# BLINKING.net
KiCad netlist of a schematic drawn in Altium Designer
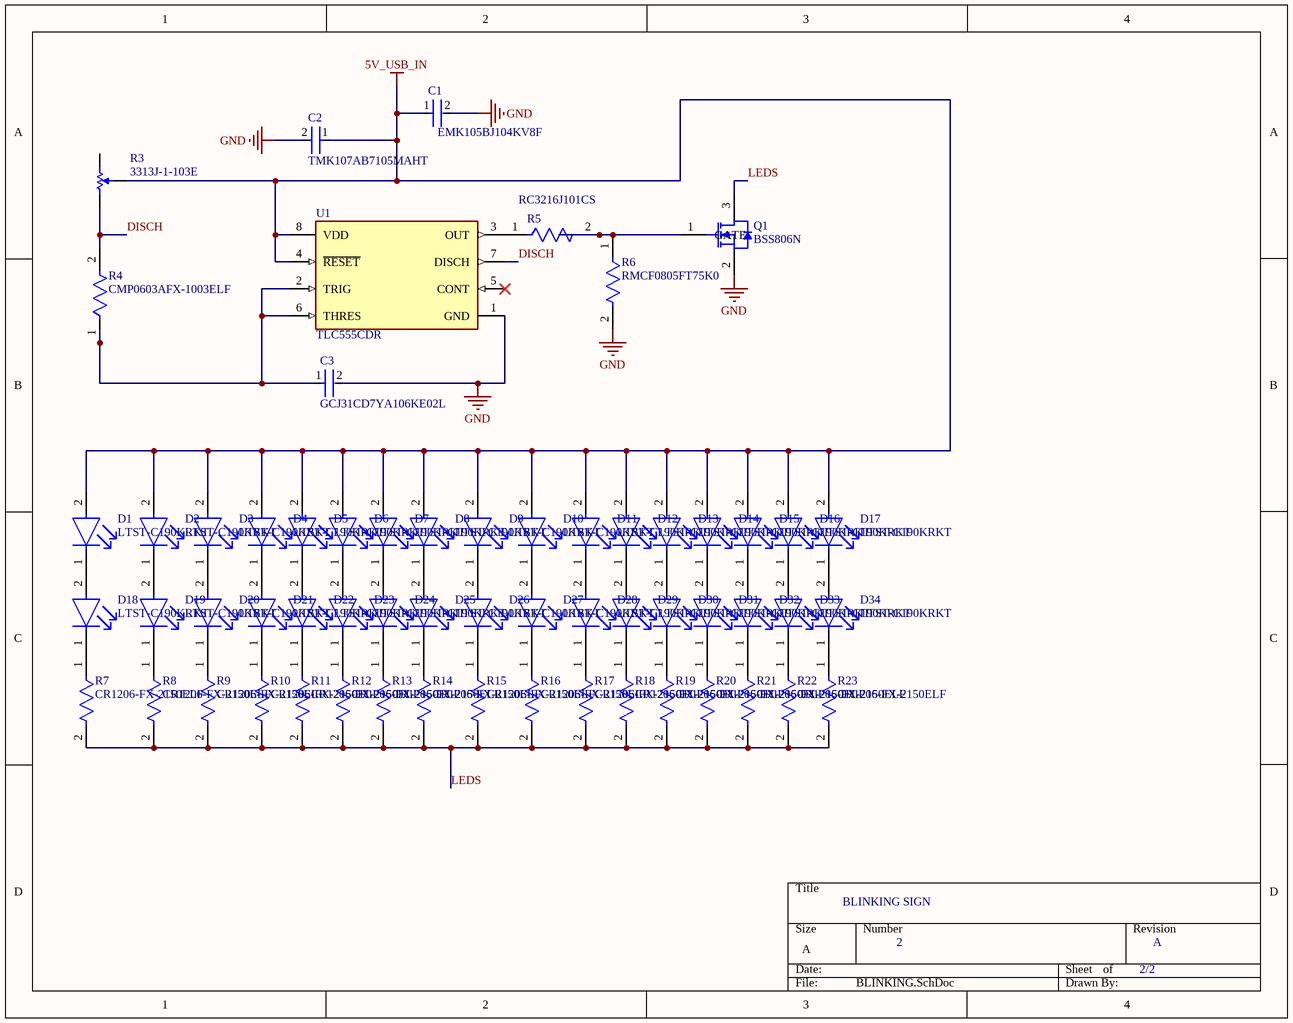
[diagram p0: BLINKING.SchDoc]

(export (version "E")
  (design (tool "Eeschema 10.0.6"))
  (components
    (comp (ref "C1")
      (value "EMK105BJ104KV8F")
      (footprint "FP-0402-L_1_0_0_05-W_0_5-MFG")
      (description "None")
      (libsource (lib "Altium Content Vault") (part "b4654b650e69147ec39a6b967a45e02"))
    )
    (comp (ref "C2")
      (value "TMK107AB7105MAHT")
      (footprint "FP-0603-L_1_6_0_15-W_0_8-IPC_B")
      (description "None")
      (fields (field (name "TOLERANCE") "20%"))
      (libsource (lib "Altium Content Vault") (part "b4654b650e69147ec39a6b967a45e02"))
    )
    (comp (ref "C3")
      (value "GCJ31CD7YA106KE02L")
      (footprint "FP-GCJ31C-0_4-IPC_C")
      (description "Cap Ceramic 10uF 35V X7T 10% SMD 1206 +125°C Embossed Plastic T/R")
      (libsource (lib "Altium Content Vault") (part "02cd4be3c70576c341d710602a673aa"))
    )
    (comp (ref "D1")
      (value "LTST-C190KRKT")
      (footprint "FP-LTST-C190KRKT-MFG")
      (description "LED RED CLEAR CHIP SMD")
      (libsource (lib "Altium Content Vault") (part "8706943c75ba83719d021d2fdc84c58"))
    )
    (comp (ref "D2")
      (value "LTST-C190KRKT")
      (footprint "FP-LTST-C190KRKT-MFG")
      (description "LED RED CLEAR CHIP SMD")
      (libsource (lib "Altium Content Vault") (part "8706943c75ba83719d021d2fdc84c58"))
    )
    (comp (ref "D3")
      (value "LTST-C190KRKT")
      (footprint "FP-LTST-C190KRKT-MFG")
      (description "LED RED CLEAR CHIP SMD")
      (libsource (lib "Altium Content Vault") (part "8706943c75ba83719d021d2fdc84c58"))
    )
    (comp (ref "D4")
      (value "LTST-C190KRKT")
      (footprint "FP-LTST-C190KRKT-MFG")
      (description "LED RED CLEAR CHIP SMD")
      (libsource (lib "Altium Content Vault") (part "8706943c75ba83719d021d2fdc84c58"))
    )
    (comp (ref "D5")
      (value "LTST-C190KRKT")
      (footprint "FP-LTST-C190KRKT-MFG")
      (description "LED RED CLEAR CHIP SMD")
      (libsource (lib "Altium Content Vault") (part "8706943c75ba83719d021d2fdc84c58"))
    )
    (comp (ref "D6")
      (value "LTST-C190KRKT")
      (footprint "FP-LTST-C190KRKT-MFG")
      (description "LED RED CLEAR CHIP SMD")
      (libsource (lib "Altium Content Vault") (part "8706943c75ba83719d021d2fdc84c58"))
    )
    (comp (ref "D7")
      (value "LTST-C190KRKT")
      (footprint "FP-LTST-C190KRKT-MFG")
      (description "LED RED CLEAR CHIP SMD")
      (libsource (lib "Altium Content Vault") (part "8706943c75ba83719d021d2fdc84c58"))
    )
    (comp (ref "D8")
      (value "LTST-C190KRKT")
      (footprint "FP-LTST-C190KRKT-MFG")
      (description "LED RED CLEAR CHIP SMD")
      (libsource (lib "Altium Content Vault") (part "8706943c75ba83719d021d2fdc84c58"))
    )
    (comp (ref "D9")
      (value "LTST-C190KRKT")
      (footprint "FP-LTST-C190KRKT-MFG")
      (description "LED RED CLEAR CHIP SMD")
      (libsource (lib "Altium Content Vault") (part "8706943c75ba83719d021d2fdc84c58"))
    )
    (comp (ref "D10")
      (value "LTST-C190KRKT")
      (footprint "FP-LTST-C190KRKT-MFG")
      (description "LED RED CLEAR CHIP SMD")
      (libsource (lib "Altium Content Vault") (part "8706943c75ba83719d021d2fdc84c58"))
    )
    (comp (ref "D11")
      (value "LTST-C190KRKT")
      (footprint "FP-LTST-C190KRKT-MFG")
      (description "LED RED CLEAR CHIP SMD")
      (libsource (lib "Altium Content Vault") (part "8706943c75ba83719d021d2fdc84c58"))
    )
    (comp (ref "D12")
      (value "LTST-C190KRKT")
      (footprint "FP-LTST-C190KRKT-MFG")
      (description "LED RED CLEAR CHIP SMD")
      (libsource (lib "Altium Content Vault") (part "8706943c75ba83719d021d2fdc84c58"))
    )
    (comp (ref "D13")
      (value "LTST-C190KRKT")
      (footprint "FP-LTST-C190KRKT-MFG")
      (description "LED RED CLEAR CHIP SMD")
      (libsource (lib "Altium Content Vault") (part "8706943c75ba83719d021d2fdc84c58"))
    )
    (comp (ref "D14")
      (value "LTST-C190KRKT")
      (footprint "FP-LTST-C190KRKT-MFG")
      (description "LED RED CLEAR CHIP SMD")
      (libsource (lib "Altium Content Vault") (part "8706943c75ba83719d021d2fdc84c58"))
    )
    (comp (ref "D15")
      (value "LTST-C190KRKT")
      (footprint "FP-LTST-C190KRKT-MFG")
      (description "LED RED CLEAR CHIP SMD")
      (libsource (lib "Altium Content Vault") (part "8706943c75ba83719d021d2fdc84c58"))
    )
    (comp (ref "D16")
      (value "LTST-C190KRKT")
      (footprint "FP-LTST-C190KRKT-MFG")
      (description "LED RED CLEAR CHIP SMD")
      (libsource (lib "Altium Content Vault") (part "8706943c75ba83719d021d2fdc84c58"))
    )
    (comp (ref "D17")
      (value "LTST-C190KRKT")
      (footprint "FP-LTST-C190KRKT-MFG")
      (description "LED RED CLEAR CHIP SMD")
      (libsource (lib "Altium Content Vault") (part "8706943c75ba83719d021d2fdc84c58"))
    )
    (comp (ref "D18")
      (value "LTST-C190KRKT")
      (footprint "FP-LTST-C190KRKT-MFG")
      (description "LED RED CLEAR CHIP SMD")
      (libsource (lib "Altium Content Vault") (part "8706943c75ba83719d021d2fdc84c58"))
    )
    (comp (ref "D19")
      (value "LTST-C190KRKT")
      (footprint "FP-LTST-C190KRKT-MFG")
      (description "LED RED CLEAR CHIP SMD")
      (libsource (lib "Altium Content Vault") (part "8706943c75ba83719d021d2fdc84c58"))
    )
    (comp (ref "D20")
      (value "LTST-C190KRKT")
      (footprint "FP-LTST-C190KRKT-MFG")
      (description "LED RED CLEAR CHIP SMD")
      (libsource (lib "Altium Content Vault") (part "8706943c75ba83719d021d2fdc84c58"))
    )
    (comp (ref "D21")
      (value "LTST-C190KRKT")
      (footprint "FP-LTST-C190KRKT-MFG")
      (description "LED RED CLEAR CHIP SMD")
      (libsource (lib "Altium Content Vault") (part "8706943c75ba83719d021d2fdc84c58"))
    )
    (comp (ref "D22")
      (value "LTST-C190KRKT")
      (footprint "FP-LTST-C190KRKT-MFG")
      (description "LED RED CLEAR CHIP SMD")
      (libsource (lib "Altium Content Vault") (part "8706943c75ba83719d021d2fdc84c58"))
    )
    (comp (ref "D23")
      (value "LTST-C190KRKT")
      (footprint "FP-LTST-C190KRKT-MFG")
      (description "LED RED CLEAR CHIP SMD")
      (libsource (lib "Altium Content Vault") (part "8706943c75ba83719d021d2fdc84c58"))
    )
    (comp (ref "D24")
      (value "LTST-C190KRKT")
      (footprint "FP-LTST-C190KRKT-MFG")
      (description "LED RED CLEAR CHIP SMD")
      (libsource (lib "Altium Content Vault") (part "8706943c75ba83719d021d2fdc84c58"))
    )
    (comp (ref "D25")
      (value "LTST-C190KRKT")
      (footprint "FP-LTST-C190KRKT-MFG")
      (description "LED RED CLEAR CHIP SMD")
      (libsource (lib "Altium Content Vault") (part "8706943c75ba83719d021d2fdc84c58"))
    )
    (comp (ref "D26")
      (value "LTST-C190KRKT")
      (footprint "FP-LTST-C190KRKT-MFG")
      (description "LED RED CLEAR CHIP SMD")
      (libsource (lib "Altium Content Vault") (part "8706943c75ba83719d021d2fdc84c58"))
    )
    (comp (ref "D27")
      (value "LTST-C190KRKT")
      (footprint "FP-LTST-C190KRKT-MFG")
      (description "LED RED CLEAR CHIP SMD")
      (libsource (lib "Altium Content Vault") (part "8706943c75ba83719d021d2fdc84c58"))
    )
    (comp (ref "D28")
      (value "LTST-C190KRKT")
      (footprint "FP-LTST-C190KRKT-MFG")
      (description "LED RED CLEAR CHIP SMD")
      (libsource (lib "Altium Content Vault") (part "8706943c75ba83719d021d2fdc84c58"))
    )
    (comp (ref "D29")
      (value "LTST-C190KRKT")
      (footprint "FP-LTST-C190KRKT-MFG")
      (description "LED RED CLEAR CHIP SMD")
      (libsource (lib "Altium Content Vault") (part "8706943c75ba83719d021d2fdc84c58"))
    )
    (comp (ref "D30")
      (value "LTST-C190KRKT")
      (footprint "FP-LTST-C190KRKT-MFG")
      (description "LED RED CLEAR CHIP SMD")
      (libsource (lib "Altium Content Vault") (part "8706943c75ba83719d021d2fdc84c58"))
    )
    (comp (ref "D31")
      (value "LTST-C190KRKT")
      (footprint "FP-LTST-C190KRKT-MFG")
      (description "LED RED CLEAR CHIP SMD")
      (libsource (lib "Altium Content Vault") (part "8706943c75ba83719d021d2fdc84c58"))
    )
    (comp (ref "D32")
      (value "LTST-C190KRKT")
      (footprint "FP-LTST-C190KRKT-MFG")
      (description "LED RED CLEAR CHIP SMD")
      (libsource (lib "Altium Content Vault") (part "8706943c75ba83719d021d2fdc84c58"))
    )
    (comp (ref "D33")
      (value "LTST-C190KRKT")
      (footprint "FP-LTST-C190KRKT-MFG")
      (description "LED RED CLEAR CHIP SMD")
      (libsource (lib "Altium Content Vault") (part "8706943c75ba83719d021d2fdc84c58"))
    )
    (comp (ref "D34")
      (value "LTST-C190KRKT")
      (footprint "FP-LTST-C190KRKT-MFG")
      (description "LED RED CLEAR CHIP SMD")
      (libsource (lib "Altium Content Vault") (part "8706943c75ba83719d021d2fdc84c58"))
    )
    (comp (ref "Q1")
      (value "BSS806N")
      (footprint "INF-PG-SOT23_M")
      (fields (field (name "MANUFACTURER") "Infineon"))
      (libsource (lib "Altium Content Vault") (part "INF-NEMOS-GSD-3"))
    )
    (comp (ref "R3")
      (value "3313J-1-103E")
      (footprint "BOUR-3313J-1_V")
      (description "Trimming Potentiometer, 10 KOhm, -55 to 125 degC, 3-Pin SMD, RoHS, Tape and Reel")
      (fields (field (name "MANUFACTURER") "Bourns"))
      (libsource (lib "Altium Content Vault") (part "RES-ADJ-3_A"))
    )
    (comp (ref "R4")
      (value "CMP0603AFX-1003ELF")
      (footprint "FP-CMP0603A-MFG")
      (description "RESHIGHPOWERA 0603 100K 1% 1/4W")
      (libsource (lib "Altium Content Vault") (part "1029c3af85768c4190bb7ad29bc67b5"))
    )
    (comp (ref "R5")
      (value "RC3216J101CS")
      (footprint "FP-RC3216-IPC_B")
      (description "Res Thick Film 1206 100Ω 5% 0.25W ±100ppm/°C Molded SMD T/R")
      (fields (field (name "TOLERANCE") "5%"))
      (libsource (lib "Altium Content Vault") (part "1029c3af85768c4190bb7ad29bc67b5"))
    )
    (comp (ref "R6")
      (value "RMCF0805FT75K0")
      (footprint "FP-RMCF0805-IPC_B")
      (description "75kΩ ±1% 0.125W 0805 Thick Film Chip Resistor AEC-Q200 compliant")
      (fields (field (name "TOLERANCE") "1%"))
      (libsource (lib "Altium Content Vault") (part "1029c3af85768c4190bb7ad29bc67b5"))
    )
    (comp (ref "R7")
      (value "CR1206-FX-2150ELF")
      (footprint "FP-CR1206-IPC_B")
      (description "Thick Film Chip Resistors 1206 215Ω 0.25W 1% 100ppm/°C")
      (fields (field (name "TOLERANCE") "1%"))
      (libsource (lib "Altium Content Vault") (part "1029c3af85768c4190bb7ad29bc67b5"))
    )
    (comp (ref "R8")
      (value "CR1206-FX-2150ELF")
      (footprint "FP-CR1206-IPC_B")
      (description "Thick Film Chip Resistors 1206 215Ω 0.25W 1% 100ppm/°C")
      (fields (field (name "TOLERANCE") "1%"))
      (libsource (lib "Altium Content Vault") (part "1029c3af85768c4190bb7ad29bc67b5"))
    )
    (comp (ref "R9")
      (value "CR1206-FX-2150ELF")
      (footprint "FP-CR1206-IPC_B")
      (description "Thick Film Chip Resistors 1206 215Ω 0.25W 1% 100ppm/°C")
      (fields (field (name "TOLERANCE") "1%"))
      (libsource (lib "Altium Content Vault") (part "1029c3af85768c4190bb7ad29bc67b5"))
    )
    (comp (ref "R10")
      (value "CR1206-FX-2150ELF")
      (footprint "FP-CR1206-IPC_B")
      (description "Thick Film Chip Resistors 1206 215Ω 0.25W 1% 100ppm/°C")
      (fields (field (name "TOLERANCE") "1%"))
      (libsource (lib "Altium Content Vault") (part "1029c3af85768c4190bb7ad29bc67b5"))
    )
    (comp (ref "R11")
      (value "CR1206-FX-2150ELF")
      (footprint "FP-CR1206-IPC_B")
      (description "Thick Film Chip Resistors 1206 215Ω 0.25W 1% 100ppm/°C")
      (fields (field (name "TOLERANCE") "1%"))
      (libsource (lib "Altium Content Vault") (part "1029c3af85768c4190bb7ad29bc67b5"))
    )
    (comp (ref "R12")
      (value "CR1206-FX-2150ELF")
      (footprint "FP-CR1206-IPC_B")
      (description "Thick Film Chip Resistors 1206 215Ω 0.25W 1% 100ppm/°C")
      (fields (field (name "TOLERANCE") "1%"))
      (libsource (lib "Altium Content Vault") (part "1029c3af85768c4190bb7ad29bc67b5"))
    )
    (comp (ref "R13")
      (value "CR1206-FX-2150ELF")
      (footprint "FP-CR1206-IPC_B")
      (description "Thick Film Chip Resistors 1206 215Ω 0.25W 1% 100ppm/°C")
      (fields (field (name "TOLERANCE") "1%"))
      (libsource (lib "Altium Content Vault") (part "1029c3af85768c4190bb7ad29bc67b5"))
    )
    (comp (ref "R14")
      (value "CR1206-FX-2150ELF")
      (footprint "FP-CR1206-IPC_B")
      (description "Thick Film Chip Resistors 1206 215Ω 0.25W 1% 100ppm/°C")
      (fields (field (name "TOLERANCE") "1%"))
      (libsource (lib "Altium Content Vault") (part "1029c3af85768c4190bb7ad29bc67b5"))
    )
    (comp (ref "R15")
      (value "CR1206-FX-2150ELF")
      (footprint "FP-CR1206-IPC_B")
      (description "Thick Film Chip Resistors 1206 215Ω 0.25W 1% 100ppm/°C")
      (fields (field (name "TOLERANCE") "1%"))
      (libsource (lib "Altium Content Vault") (part "1029c3af85768c4190bb7ad29bc67b5"))
    )
    (comp (ref "R16")
      (value "CR1206-FX-2150ELF")
      (footprint "FP-CR1206-IPC_B")
      (description "Thick Film Chip Resistors 1206 215Ω 0.25W 1% 100ppm/°C")
      (fields (field (name "TOLERANCE") "1%"))
      (libsource (lib "Altium Content Vault") (part "1029c3af85768c4190bb7ad29bc67b5"))
    )
    (comp (ref "R17")
      (value "CR1206-FX-2150ELF")
      (footprint "FP-CR1206-IPC_B")
      (description "Thick Film Chip Resistors 1206 215Ω 0.25W 1% 100ppm/°C")
      (fields (field (name "TOLERANCE") "1%"))
      (libsource (lib "Altium Content Vault") (part "1029c3af85768c4190bb7ad29bc67b5"))
    )
    (comp (ref "R18")
      (value "CR1206-FX-2150ELF")
      (footprint "FP-CR1206-IPC_B")
      (description "Thick Film Chip Resistors 1206 215Ω 0.25W 1% 100ppm/°C")
      (fields (field (name "TOLERANCE") "1%"))
      (libsource (lib "Altium Content Vault") (part "1029c3af85768c4190bb7ad29bc67b5"))
    )
    (comp (ref "R19")
      (value "CR1206-FX-2150ELF")
      (footprint "FP-CR1206-IPC_B")
      (description "Thick Film Chip Resistors 1206 215Ω 0.25W 1% 100ppm/°C")
      (fields (field (name "TOLERANCE") "1%"))
      (libsource (lib "Altium Content Vault") (part "1029c3af85768c4190bb7ad29bc67b5"))
    )
    (comp (ref "R20")
      (value "CR1206-FX-2150ELF")
      (footprint "FP-CR1206-IPC_B")
      (description "Thick Film Chip Resistors 1206 215Ω 0.25W 1% 100ppm/°C")
      (fields (field (name "TOLERANCE") "1%"))
      (libsource (lib "Altium Content Vault") (part "1029c3af85768c4190bb7ad29bc67b5"))
    )
    (comp (ref "R21")
      (value "CR1206-FX-2150ELF")
      (footprint "FP-CR1206-IPC_B")
      (description "Thick Film Chip Resistors 1206 215Ω 0.25W 1% 100ppm/°C")
      (fields (field (name "TOLERANCE") "1%"))
      (libsource (lib "Altium Content Vault") (part "1029c3af85768c4190bb7ad29bc67b5"))
    )
    (comp (ref "R22")
      (value "CR1206-FX-2150ELF")
      (footprint "FP-CR1206-IPC_B")
      (description "Thick Film Chip Resistors 1206 215Ω 0.25W 1% 100ppm/°C")
      (fields (field (name "TOLERANCE") "1%"))
      (libsource (lib "Altium Content Vault") (part "1029c3af85768c4190bb7ad29bc67b5"))
    )
    (comp (ref "R23")
      (value "CR1206-FX-2150ELF")
      (footprint "FP-CR1206-IPC_B")
      (description "Thick Film Chip Resistors 1206 215Ω 0.25W 1% 100ppm/°C")
      (fields (field (name "TOLERANCE") "1%"))
      (libsource (lib "Altium Content Vault") (part "1029c3af85768c4190bb7ad29bc67b5"))
    )
    (comp (ref "U1")
      (value "TLC555CDR")
      (footprint "FP-D0008A-IPC_B")
      (description "IC OSC SGL TIMER 2.1MHZ 8-SOIC")
      (libsource (lib "Altium Content Vault") (part "fd1638d23bf5e420a54176ee4f8e783"))
    )
  )
  (nets
    (net (code "1") (name "/DISCH") (class "Default")
      (node (ref "R3") (pin "1") (pinfunction "1_1") (pintype "passive"))
      (node (ref "R4") (pin "2") (pinfunction "2_2") (pintype "passive"))
      (node (ref "U1") (pin "7") (pinfunction "DISCH_7") (pintype "output"))
    )
    (net (code "2") (name "/LEDS") (class "Default")
      (node (ref "Q1") (pin "3") (pinfunction "DRAIN_3") (pintype "passive"))
      (node (ref "R10") (pin "2") (pinfunction "2_2") (pintype "passive"))
      (node (ref "R11") (pin "2") (pinfunction "2_2") (pintype "passive"))
      (node (ref "R12") (pin "2") (pinfunction "2_2") (pintype "passive"))
      (node (ref "R13") (pin "2") (pinfunction "2_2") (pintype "passive"))
      (node (ref "R14") (pin "2") (pinfunction "2_2") (pintype "passive"))
      (node (ref "R15") (pin "2") (pinfunction "2_2") (pintype "passive"))
      (node (ref "R16") (pin "2") (pinfunction "2_2") (pintype "passive"))
      (node (ref "R17") (pin "2") (pinfunction "2_2") (pintype "passive"))
      (node (ref "R18") (pin "2") (pinfunction "2_2") (pintype "passive"))
      (node (ref "R19") (pin "2") (pinfunction "2_2") (pintype "passive"))
      (node (ref "R20") (pin "2") (pinfunction "2_2") (pintype "passive"))
      (node (ref "R21") (pin "2") (pinfunction "2_2") (pintype "passive"))
      (node (ref "R22") (pin "2") (pinfunction "2_2") (pintype "passive"))
      (node (ref "R23") (pin "2") (pinfunction "2_2") (pintype "passive"))
      (node (ref "R7") (pin "2") (pinfunction "2_2") (pintype "passive"))
      (node (ref "R8") (pin "2") (pinfunction "2_2") (pintype "passive"))
      (node (ref "R9") (pin "2") (pinfunction "2_2") (pintype "passive"))
    )
    (net (code "3") (name "5V_USB_IN") (class "Default")
      (node (ref "C1") (pin "1") (pinfunction "1_1") (pintype "passive"))
      (node (ref "C2") (pin "1") (pinfunction "1_1") (pintype "passive"))
      (node (ref "D1") (pin "2") (pinfunction "A_2") (pintype "passive"))
      (node (ref "D10") (pin "2") (pinfunction "A_2") (pintype "passive"))
      (node (ref "D11") (pin "2") (pinfunction "A_2") (pintype "passive"))
      (node (ref "D12") (pin "2") (pinfunction "A_2") (pintype "passive"))
      (node (ref "D13") (pin "2") (pinfunction "A_2") (pintype "passive"))
      (node (ref "D14") (pin "2") (pinfunction "A_2") (pintype "passive"))
      (node (ref "D15") (pin "2") (pinfunction "A_2") (pintype "passive"))
      (node (ref "D16") (pin "2") (pinfunction "A_2") (pintype "passive"))
      (node (ref "D17") (pin "2") (pinfunction "A_2") (pintype "passive"))
      (node (ref "D2") (pin "2") (pinfunction "A_2") (pintype "passive"))
      (node (ref "D3") (pin "2") (pinfunction "A_2") (pintype "passive"))
      (node (ref "D4") (pin "2") (pinfunction "A_2") (pintype "passive"))
      (node (ref "D5") (pin "2") (pinfunction "A_2") (pintype "passive"))
      (node (ref "D6") (pin "2") (pinfunction "A_2") (pintype "passive"))
      (node (ref "D7") (pin "2") (pinfunction "A_2") (pintype "passive"))
      (node (ref "D8") (pin "2") (pinfunction "A_2") (pintype "passive"))
      (node (ref "D9") (pin "2") (pinfunction "A_2") (pintype "passive"))
      (node (ref "R3") (pin "2") (pinfunction "2_2") (pintype "passive"))
      (node (ref "U1") (pin "4") (pinfunction "~{RESET}_4") (pintype "input"))
      (node (ref "U1") (pin "8") (pinfunction "VDD_8") (pintype "power_in"))
    )
    (net (code "4") (name "GND") (class "Default")
      (node (ref "C1") (pin "2") (pinfunction "2_2") (pintype "passive"))
      (node (ref "C2") (pin "2") (pinfunction "2_2") (pintype "passive"))
      (node (ref "C3") (pin "2") (pinfunction "2_2") (pintype "passive"))
      (node (ref "Q1") (pin "2") (pinfunction "SOURCE_2") (pintype "passive"))
      (node (ref "R6") (pin "2") (pinfunction "2_2") (pintype "passive"))
      (node (ref "U1") (pin "1") (pinfunction "GND_1") (pintype "power_in"))
    )
    (net (code "5") (name "Net-(D1-C)") (class "Default")
      (node (ref "D1") (pin "1") (pinfunction "C_1") (pintype "passive"))
      (node (ref "D18") (pin "2") (pinfunction "A_2") (pintype "passive"))
    )
    (net (code "6") (name "Net-(D10-C)") (class "Default")
      (node (ref "D10") (pin "1") (pinfunction "C_1") (pintype "passive"))
      (node (ref "D27") (pin "2") (pinfunction "A_2") (pintype "passive"))
    )
    (net (code "7") (name "Net-(D11-C)") (class "Default")
      (node (ref "D11") (pin "1") (pinfunction "C_1") (pintype "passive"))
      (node (ref "D28") (pin "2") (pinfunction "A_2") (pintype "passive"))
    )
    (net (code "8") (name "Net-(D12-C)") (class "Default")
      (node (ref "D12") (pin "1") (pinfunction "C_1") (pintype "passive"))
      (node (ref "D29") (pin "2") (pinfunction "A_2") (pintype "passive"))
    )
    (net (code "9") (name "Net-(D13-C)") (class "Default")
      (node (ref "D13") (pin "1") (pinfunction "C_1") (pintype "passive"))
      (node (ref "D30") (pin "2") (pinfunction "A_2") (pintype "passive"))
    )
    (net (code "10") (name "Net-(D14-C)") (class "Default")
      (node (ref "D14") (pin "1") (pinfunction "C_1") (pintype "passive"))
      (node (ref "D31") (pin "2") (pinfunction "A_2") (pintype "passive"))
    )
    (net (code "11") (name "Net-(D15-C)") (class "Default")
      (node (ref "D15") (pin "1") (pinfunction "C_1") (pintype "passive"))
      (node (ref "D32") (pin "2") (pinfunction "A_2") (pintype "passive"))
    )
    (net (code "12") (name "Net-(D16-C)") (class "Default")
      (node (ref "D16") (pin "1") (pinfunction "C_1") (pintype "passive"))
      (node (ref "D33") (pin "2") (pinfunction "A_2") (pintype "passive"))
    )
    (net (code "13") (name "Net-(D17-C)") (class "Default")
      (node (ref "D17") (pin "1") (pinfunction "C_1") (pintype "passive"))
      (node (ref "D34") (pin "2") (pinfunction "A_2") (pintype "passive"))
    )
    (net (code "14") (name "Net-(D18-C)") (class "Default")
      (node (ref "D18") (pin "1") (pinfunction "C_1") (pintype "passive"))
      (node (ref "R7") (pin "1") (pinfunction "1_1") (pintype "passive"))
    )
    (net (code "15") (name "Net-(D19-A)") (class "Default")
      (node (ref "D19") (pin "2") (pinfunction "A_2") (pintype "passive"))
      (node (ref "D2") (pin "1") (pinfunction "C_1") (pintype "passive"))
    )
    (net (code "16") (name "Net-(D19-C)") (class "Default")
      (node (ref "D19") (pin "1") (pinfunction "C_1") (pintype "passive"))
      (node (ref "R8") (pin "1") (pinfunction "1_1") (pintype "passive"))
    )
    (net (code "17") (name "Net-(D20-A)") (class "Default")
      (node (ref "D20") (pin "2") (pinfunction "A_2") (pintype "passive"))
      (node (ref "D3") (pin "1") (pinfunction "C_1") (pintype "passive"))
    )
    (net (code "18") (name "Net-(D20-C)") (class "Default")
      (node (ref "D20") (pin "1") (pinfunction "C_1") (pintype "passive"))
      (node (ref "R9") (pin "1") (pinfunction "1_1") (pintype "passive"))
    )
    (net (code "19") (name "Net-(D21-A)") (class "Default")
      (node (ref "D21") (pin "2") (pinfunction "A_2") (pintype "passive"))
      (node (ref "D4") (pin "1") (pinfunction "C_1") (pintype "passive"))
    )
    (net (code "20") (name "Net-(D21-C)") (class "Default")
      (node (ref "D21") (pin "1") (pinfunction "C_1") (pintype "passive"))
      (node (ref "R10") (pin "1") (pinfunction "1_1") (pintype "passive"))
    )
    (net (code "21") (name "Net-(D22-A)") (class "Default")
      (node (ref "D22") (pin "2") (pinfunction "A_2") (pintype "passive"))
      (node (ref "D5") (pin "1") (pinfunction "C_1") (pintype "passive"))
    )
    (net (code "22") (name "Net-(D22-C)") (class "Default")
      (node (ref "D22") (pin "1") (pinfunction "C_1") (pintype "passive"))
      (node (ref "R11") (pin "1") (pinfunction "1_1") (pintype "passive"))
    )
    (net (code "23") (name "Net-(D23-A)") (class "Default")
      (node (ref "D23") (pin "2") (pinfunction "A_2") (pintype "passive"))
      (node (ref "D6") (pin "1") (pinfunction "C_1") (pintype "passive"))
    )
    (net (code "24") (name "Net-(D23-C)") (class "Default")
      (node (ref "D23") (pin "1") (pinfunction "C_1") (pintype "passive"))
      (node (ref "R12") (pin "1") (pinfunction "1_1") (pintype "passive"))
    )
    (net (code "25") (name "Net-(D24-A)") (class "Default")
      (node (ref "D24") (pin "2") (pinfunction "A_2") (pintype "passive"))
      (node (ref "D7") (pin "1") (pinfunction "C_1") (pintype "passive"))
    )
    (net (code "26") (name "Net-(D24-C)") (class "Default")
      (node (ref "D24") (pin "1") (pinfunction "C_1") (pintype "passive"))
      (node (ref "R13") (pin "1") (pinfunction "1_1") (pintype "passive"))
    )
    (net (code "27") (name "Net-(D25-A)") (class "Default")
      (node (ref "D25") (pin "2") (pinfunction "A_2") (pintype "passive"))
      (node (ref "D8") (pin "1") (pinfunction "C_1") (pintype "passive"))
    )
    (net (code "28") (name "Net-(D25-C)") (class "Default")
      (node (ref "D25") (pin "1") (pinfunction "C_1") (pintype "passive"))
      (node (ref "R14") (pin "1") (pinfunction "1_1") (pintype "passive"))
    )
    (net (code "29") (name "Net-(D26-A)") (class "Default")
      (node (ref "D26") (pin "2") (pinfunction "A_2") (pintype "passive"))
      (node (ref "D9") (pin "1") (pinfunction "C_1") (pintype "passive"))
    )
    (net (code "30") (name "Net-(D26-C)") (class "Default")
      (node (ref "D26") (pin "1") (pinfunction "C_1") (pintype "passive"))
      (node (ref "R15") (pin "1") (pinfunction "1_1") (pintype "passive"))
    )
    (net (code "31") (name "Net-(D27-C)") (class "Default")
      (node (ref "D27") (pin "1") (pinfunction "C_1") (pintype "passive"))
      (node (ref "R16") (pin "1") (pinfunction "1_1") (pintype "passive"))
    )
    (net (code "32") (name "Net-(D28-C)") (class "Default")
      (node (ref "D28") (pin "1") (pinfunction "C_1") (pintype "passive"))
      (node (ref "R17") (pin "1") (pinfunction "1_1") (pintype "passive"))
    )
    (net (code "33") (name "Net-(D29-C)") (class "Default")
      (node (ref "D29") (pin "1") (pinfunction "C_1") (pintype "passive"))
      (node (ref "R18") (pin "1") (pinfunction "1_1") (pintype "passive"))
    )
    (net (code "34") (name "Net-(D30-C)") (class "Default")
      (node (ref "D30") (pin "1") (pinfunction "C_1") (pintype "passive"))
      (node (ref "R19") (pin "1") (pinfunction "1_1") (pintype "passive"))
    )
    (net (code "35") (name "Net-(D31-C)") (class "Default")
      (node (ref "D31") (pin "1") (pinfunction "C_1") (pintype "passive"))
      (node (ref "R20") (pin "1") (pinfunction "1_1") (pintype "passive"))
    )
    (net (code "36") (name "Net-(D32-C)") (class "Default")
      (node (ref "D32") (pin "1") (pinfunction "C_1") (pintype "passive"))
      (node (ref "R21") (pin "1") (pinfunction "1_1") (pintype "passive"))
    )
    (net (code "37") (name "Net-(D33-C)") (class "Default")
      (node (ref "D33") (pin "1") (pinfunction "C_1") (pintype "passive"))
      (node (ref "R22") (pin "1") (pinfunction "1_1") (pintype "passive"))
    )
    (net (code "38") (name "Net-(D34-C)") (class "Default")
      (node (ref "D34") (pin "1") (pinfunction "C_1") (pintype "passive"))
      (node (ref "R23") (pin "1") (pinfunction "1_1") (pintype "passive"))
    )
    (net (code "39") (name "Net-(Q1-GATE)") (class "Default")
      (node (ref "Q1") (pin "1") (pinfunction "GATE_1") (pintype "passive"))
      (node (ref "R5") (pin "2") (pinfunction "2_2") (pintype "passive"))
      (node (ref "R6") (pin "1") (pinfunction "1_1") (pintype "passive"))
    )
    (net (code "40") (name "Net-(U1-OUT)") (class "Default")
      (node (ref "R5") (pin "1") (pinfunction "1_1") (pintype "passive"))
      (node (ref "U1") (pin "3") (pinfunction "OUT_3") (pintype "output"))
    )
    (net (code "41") (name "Net-(U1-THRES)") (class "Default")
      (node (ref "C3") (pin "1") (pinfunction "1_1") (pintype "passive"))
      (node (ref "R4") (pin "1") (pinfunction "1_1") (pintype "passive"))
      (node (ref "U1") (pin "2") (pinfunction "TRIG_2") (pintype "input"))
      (node (ref "U1") (pin "6") (pinfunction "THRES_6") (pintype "input"))
    )
    (net (code "42") (name "unconnected-(R3-Pad3)") (class "Default")
      (node (ref "R3") (pin "3") (pinfunction "3_3") (pintype "passive"))
    )
    (net (code "43") (name "unconnected-(U1-CONT-Pad5)") (class "Default")
      (node (ref "U1") (pin "5") (pinfunction "CONT_5") (pintype "input+no_connect"))
    )
  )
)
